# powersupply_r0.net
KiCad netlist of a schematic drawn in EAGLE
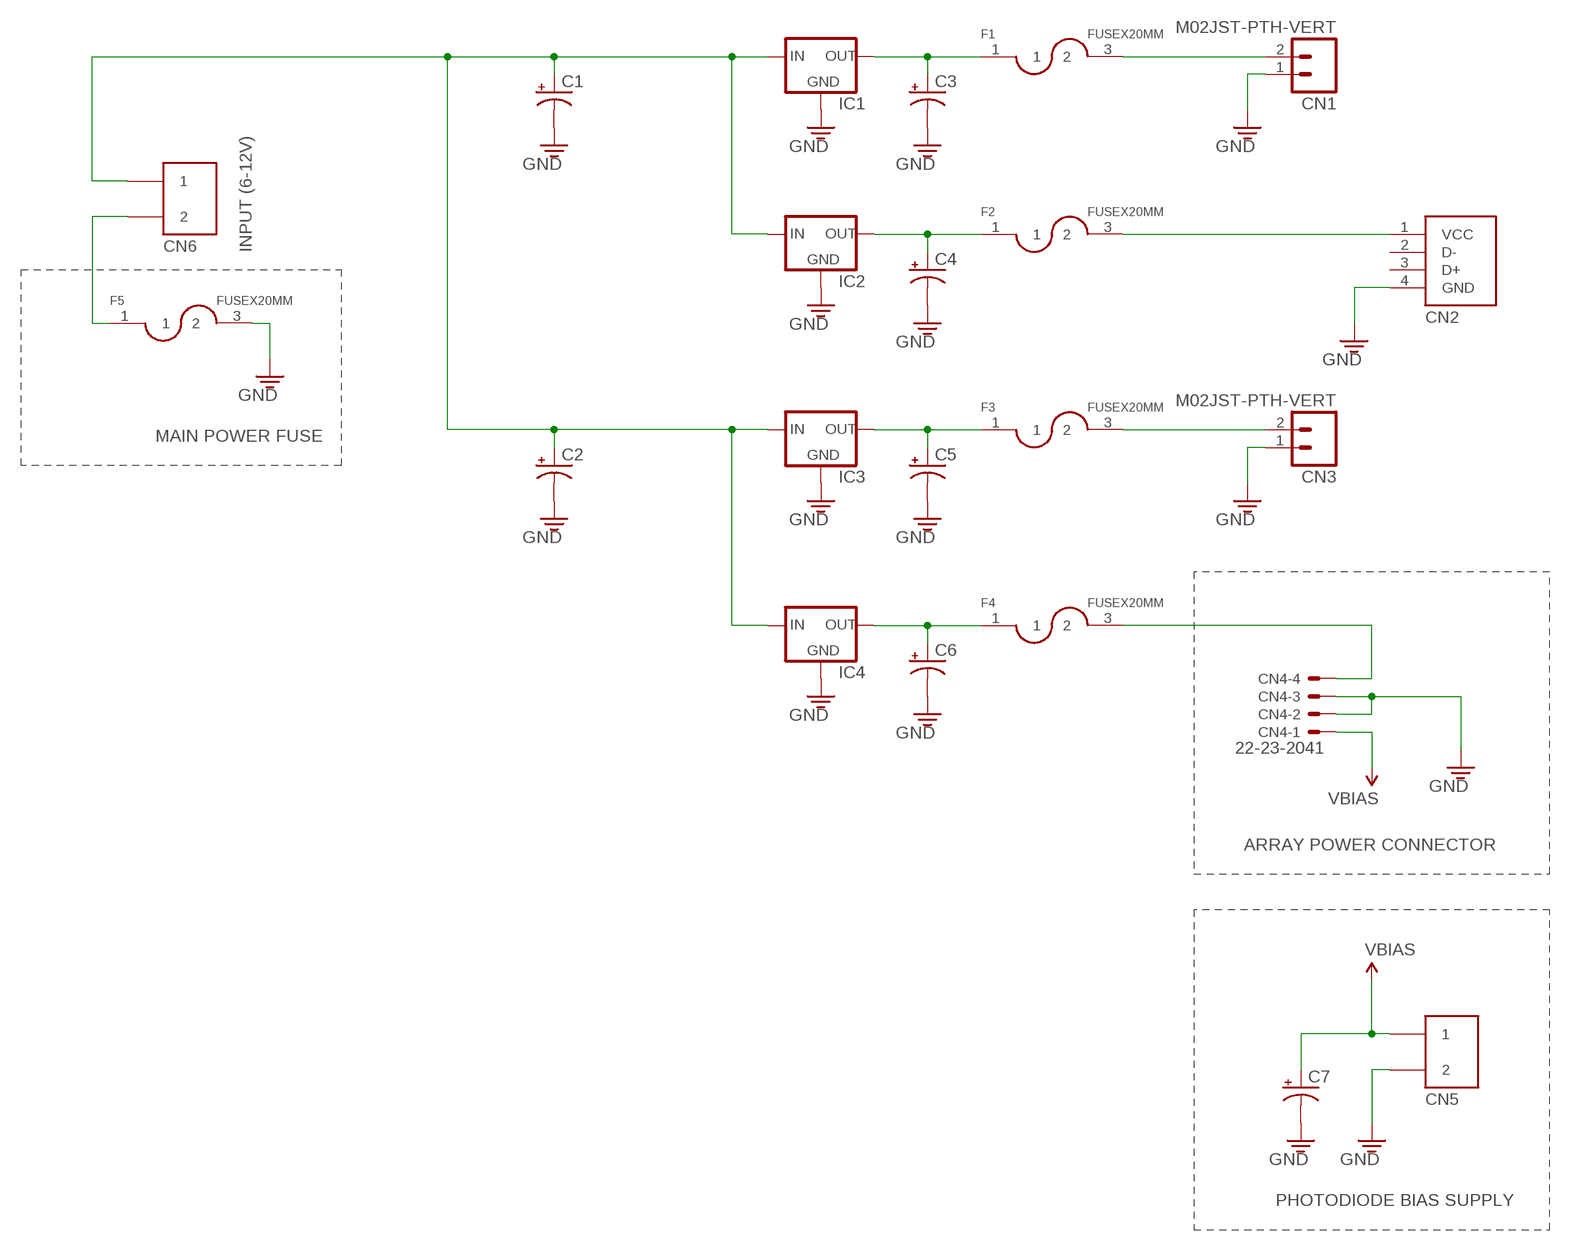
[diagram p0: schematic, sheet 1]

(export (version "E")
  (design (tool "Eeschema 10.0.6"))
  (components
    (comp (ref "C1")
      (value "CAP_POLPTH4")
      (footprint "eagle-import:CPOL-RADIAL-1000UF-25V")
      (libsource (lib "eagle-import") (part "CAP_POLPTH4"))
    )
    (comp (ref "C2")
      (value "CAP_POLPTH4")
      (footprint "eagle-import:CPOL-RADIAL-1000UF-25V")
      (libsource (lib "eagle-import") (part "CAP_POLPTH4"))
    )
    (comp (ref "C3")
      (value "CAP_POLPTH1")
      (footprint "eagle-import:CPOL-RADIAL-100UF-25V")
      (libsource (lib "eagle-import") (part "CAP_POLPTH1"))
    )
    (comp (ref "C4")
      (value "CAP_POLPTH1")
      (footprint "eagle-import:CPOL-RADIAL-100UF-25V")
      (libsource (lib "eagle-import") (part "CAP_POLPTH1"))
    )
    (comp (ref "C5")
      (value "CAP_POLPTH1")
      (footprint "eagle-import:CPOL-RADIAL-100UF-25V")
      (libsource (lib "eagle-import") (part "CAP_POLPTH1"))
    )
    (comp (ref "C6")
      (value "CAP_POLPTH1")
      (footprint "eagle-import:CPOL-RADIAL-100UF-25V")
      (libsource (lib "eagle-import") (part "CAP_POLPTH1"))
    )
    (comp (ref "C7")
      (value "CAP_POLPTH1")
      (footprint "eagle-import:CPOL-RADIAL-100UF-25V")
      (libsource (lib "eagle-import") (part "CAP_POLPTH1"))
    )
    (comp (ref "CN1")
      (value "M02JST-PTH-VERT")
      (footprint "eagle-import:JST-2-PTH-VERT")
      (libsource (lib "eagle-import") (part "M02JST-PTH-VERT"))
    )
    (comp (ref "CN2")
      (value "CON-USB")
      (footprint "eagle-import:MOLEX-USB-105057-0001")
      (libsource (lib "eagle-import") (part "CON-USB"))
    )
    (comp (ref "CN3")
      (value "M02JST-PTH-VERT")
      (footprint "eagle-import:JST-2-PTH-VERT")
      (libsource (lib "eagle-import") (part "M02JST-PTH-VERT"))
    )
    (comp (ref "CN4")
      (value "22-23-2041")
      (footprint "eagle-import:22-23-2041")
      (fields (field (name "MF") "MOLEX"))
      (libsource (lib "eagle-import") (part "22-23-2041"))
    )
    (comp (ref "CN5")
      (value "SCREWTERMINAL-2PIN")
      (footprint "eagle-import:SCREWTERMINAL-2PIN")
      (libsource (lib "eagle-import") (part "SCREWTERMINAL-2PIN"))
    )
    (comp (ref "CN6")
      (value "SCREWTERMINAL-2PIN")
      (footprint "eagle-import:SCREWTERMINAL-2PIN")
      (libsource (lib "eagle-import") (part "SCREWTERMINAL-2PIN"))
    )
    (comp (ref "F1")
      (value "FUSEX20MM")
      (footprint "eagle-import:FUSE_5MM")
      (libsource (lib "eagle-import") (part "FUSEX20MM"))
    )
    (comp (ref "F2")
      (value "FUSEX20MM")
      (footprint "eagle-import:FUSE_5MM")
      (libsource (lib "eagle-import") (part "FUSEX20MM"))
    )
    (comp (ref "F3")
      (value "FUSEX20MM")
      (footprint "eagle-import:FUSE_5MM")
      (libsource (lib "eagle-import") (part "FUSEX20MM"))
    )
    (comp (ref "F4")
      (value "FUSEX20MM")
      (footprint "eagle-import:FUSE_5MM")
      (libsource (lib "eagle-import") (part "FUSEX20MM"))
    )
    (comp (ref "F5")
      (value "FUSEX20MM")
      (footprint "eagle-import:FUSE_5MM")
      (libsource (lib "eagle-import") (part "FUSEX20MM"))
    )
    (comp (ref "IC1")
      (value "V_REG_78XXSINK")
      (footprint "eagle-import:TO220-IGO")
      (libsource (lib "eagle-import") (part "V_REG_78XXSINK"))
    )
    (comp (ref "IC2")
      (value "V_REG_78XXSINK")
      (footprint "eagle-import:TO220-IGO")
      (libsource (lib "eagle-import") (part "V_REG_78XXSINK"))
    )
    (comp (ref "IC3")
      (value "V_REG_78XXSINK")
      (footprint "eagle-import:TO220-IGO")
      (libsource (lib "eagle-import") (part "V_REG_78XXSINK"))
    )
    (comp (ref "IC4")
      (value "V_REG_78XXSINK")
      (footprint "eagle-import:TO220-IGO")
      (libsource (lib "eagle-import") (part "V_REG_78XXSINK"))
    )
  )
  (nets
    (net (code "1") (name "GND") (class "Default")
      (node (ref "C1") (pin "2") (pinfunction "-_2") (pintype "passive"))
      (node (ref "C2") (pin "2") (pinfunction "-_2") (pintype "passive"))
      (node (ref "C3") (pin "2") (pinfunction "-_2") (pintype "passive"))
      (node (ref "C4") (pin "2") (pinfunction "-_2") (pintype "passive"))
      (node (ref "C5") (pin "2") (pinfunction "-_2") (pintype "passive"))
      (node (ref "C6") (pin "2") (pinfunction "-_2") (pintype "passive"))
      (node (ref "C7") (pin "2") (pinfunction "-_2") (pintype "passive"))
      (node (ref "CN1") (pin "1") (pinfunction "2_1") (pintype "passive"))
      (node (ref "CN2") (pin "4") (pinfunction "GND_4") (pintype "bidirectional"))
      (node (ref "CN3") (pin "1") (pinfunction "2_1") (pintype "passive"))
      (node (ref "CN4") (pin "2") (pinfunction "S_2") (pintype "passive"))
      (node (ref "CN4") (pin "3") (pinfunction "S_3") (pintype "passive"))
      (node (ref "CN5") (pin "2") (pinfunction "2_2") (pintype "bidirectional"))
      (node (ref "F5") (pin "3") (pinfunction "2_3") (pintype "bidirectional"))
      (node (ref "IC1") (pin "GND") (pinfunction "GND_GND") (pintype "input"))
      (node (ref "IC2") (pin "GND") (pinfunction "GND_GND") (pintype "input"))
      (node (ref "IC3") (pin "GND") (pinfunction "GND_GND") (pintype "input"))
      (node (ref "IC4") (pin "GND") (pinfunction "GND_GND") (pintype "input"))
    )
    (net (code "2") (name "Net-(C1-+)") (class "Default")
      (node (ref "C1") (pin "1") (pinfunction "+_1") (pintype "passive"))
      (node (ref "C2") (pin "1") (pinfunction "+_1") (pintype "passive"))
      (node (ref "CN6") (pin "1") (pinfunction "1_1") (pintype "bidirectional"))
      (node (ref "IC1") (pin "IN") (pinfunction "IN_IN") (pintype "input"))
      (node (ref "IC2") (pin "IN") (pinfunction "IN_IN") (pintype "input"))
      (node (ref "IC3") (pin "IN") (pinfunction "IN_IN") (pintype "input"))
      (node (ref "IC4") (pin "IN") (pinfunction "IN_IN") (pintype "input"))
    )
    (net (code "3") (name "Net-(C3-+)") (class "Default")
      (node (ref "C3") (pin "1") (pinfunction "+_1") (pintype "passive"))
      (node (ref "F1") (pin "1") (pinfunction "1_1") (pintype "bidirectional"))
      (node (ref "IC1") (pin "OUT") (pinfunction "OUT_OUT") (pintype "output"))
    )
    (net (code "4") (name "Net-(C4-+)") (class "Default")
      (node (ref "C4") (pin "1") (pinfunction "+_1") (pintype "passive"))
      (node (ref "F2") (pin "1") (pinfunction "1_1") (pintype "bidirectional"))
      (node (ref "IC2") (pin "OUT") (pinfunction "OUT_OUT") (pintype "output"))
    )
    (net (code "5") (name "Net-(C5-+)") (class "Default")
      (node (ref "C5") (pin "1") (pinfunction "+_1") (pintype "passive"))
      (node (ref "F3") (pin "1") (pinfunction "1_1") (pintype "bidirectional"))
      (node (ref "IC3") (pin "OUT") (pinfunction "OUT_OUT") (pintype "output"))
    )
    (net (code "6") (name "Net-(C6-+)") (class "Default")
      (node (ref "C6") (pin "1") (pinfunction "+_1") (pintype "passive"))
      (node (ref "F4") (pin "1") (pinfunction "1_1") (pintype "bidirectional"))
      (node (ref "IC4") (pin "OUT") (pinfunction "OUT_OUT") (pintype "output"))
    )
    (net (code "7") (name "Net-(CN1-1)") (class "Default")
      (node (ref "CN1") (pin "2") (pinfunction "1_2") (pintype "passive"))
      (node (ref "F1") (pin "3") (pinfunction "2_3") (pintype "bidirectional"))
    )
    (net (code "8") (name "Net-(CN2-VCC)") (class "Default")
      (node (ref "CN2") (pin "1") (pinfunction "VCC_1") (pintype "bidirectional"))
      (node (ref "F2") (pin "3") (pinfunction "2_3") (pintype "bidirectional"))
    )
    (net (code "9") (name "Net-(CN3-1)") (class "Default")
      (node (ref "CN3") (pin "2") (pinfunction "1_2") (pintype "passive"))
      (node (ref "F3") (pin "3") (pinfunction "2_3") (pintype "bidirectional"))
    )
    (net (code "10") (name "Net-(CN4D-S)") (class "Default")
      (node (ref "CN4") (pin "4") (pinfunction "S_4") (pintype "passive"))
      (node (ref "F4") (pin "3") (pinfunction "2_3") (pintype "bidirectional"))
    )
    (net (code "11") (name "Net-(CN6-Pad2)") (class "Default")
      (node (ref "CN6") (pin "2") (pinfunction "2_2") (pintype "bidirectional"))
      (node (ref "F5") (pin "1") (pinfunction "1_1") (pintype "bidirectional"))
    )
    (net (code "12") (name "VBIAS") (class "Default")
      (node (ref "C7") (pin "1") (pinfunction "+_1") (pintype "passive"))
      (node (ref "CN4") (pin "1") (pinfunction "S_1") (pintype "passive"))
      (node (ref "CN5") (pin "1") (pinfunction "1_1") (pintype "bidirectional"))
    )
    (net (code "13") (name "unconnected-(CN2-D+-Pad3)") (class "Default")
      (node (ref "CN2") (pin "3") (pinfunction "D+_3") (pintype "bidirectional"))
    )
    (net (code "14") (name "unconnected-(CN2-D--Pad2)") (class "Default")
      (node (ref "CN2") (pin "2") (pinfunction "D-_2") (pintype "bidirectional"))
    )
  )
)
